# Yitran_IT900_Hutschiene_PIM7A_1_0.net
KiCad netlist of a schematic drawn in EAGLE
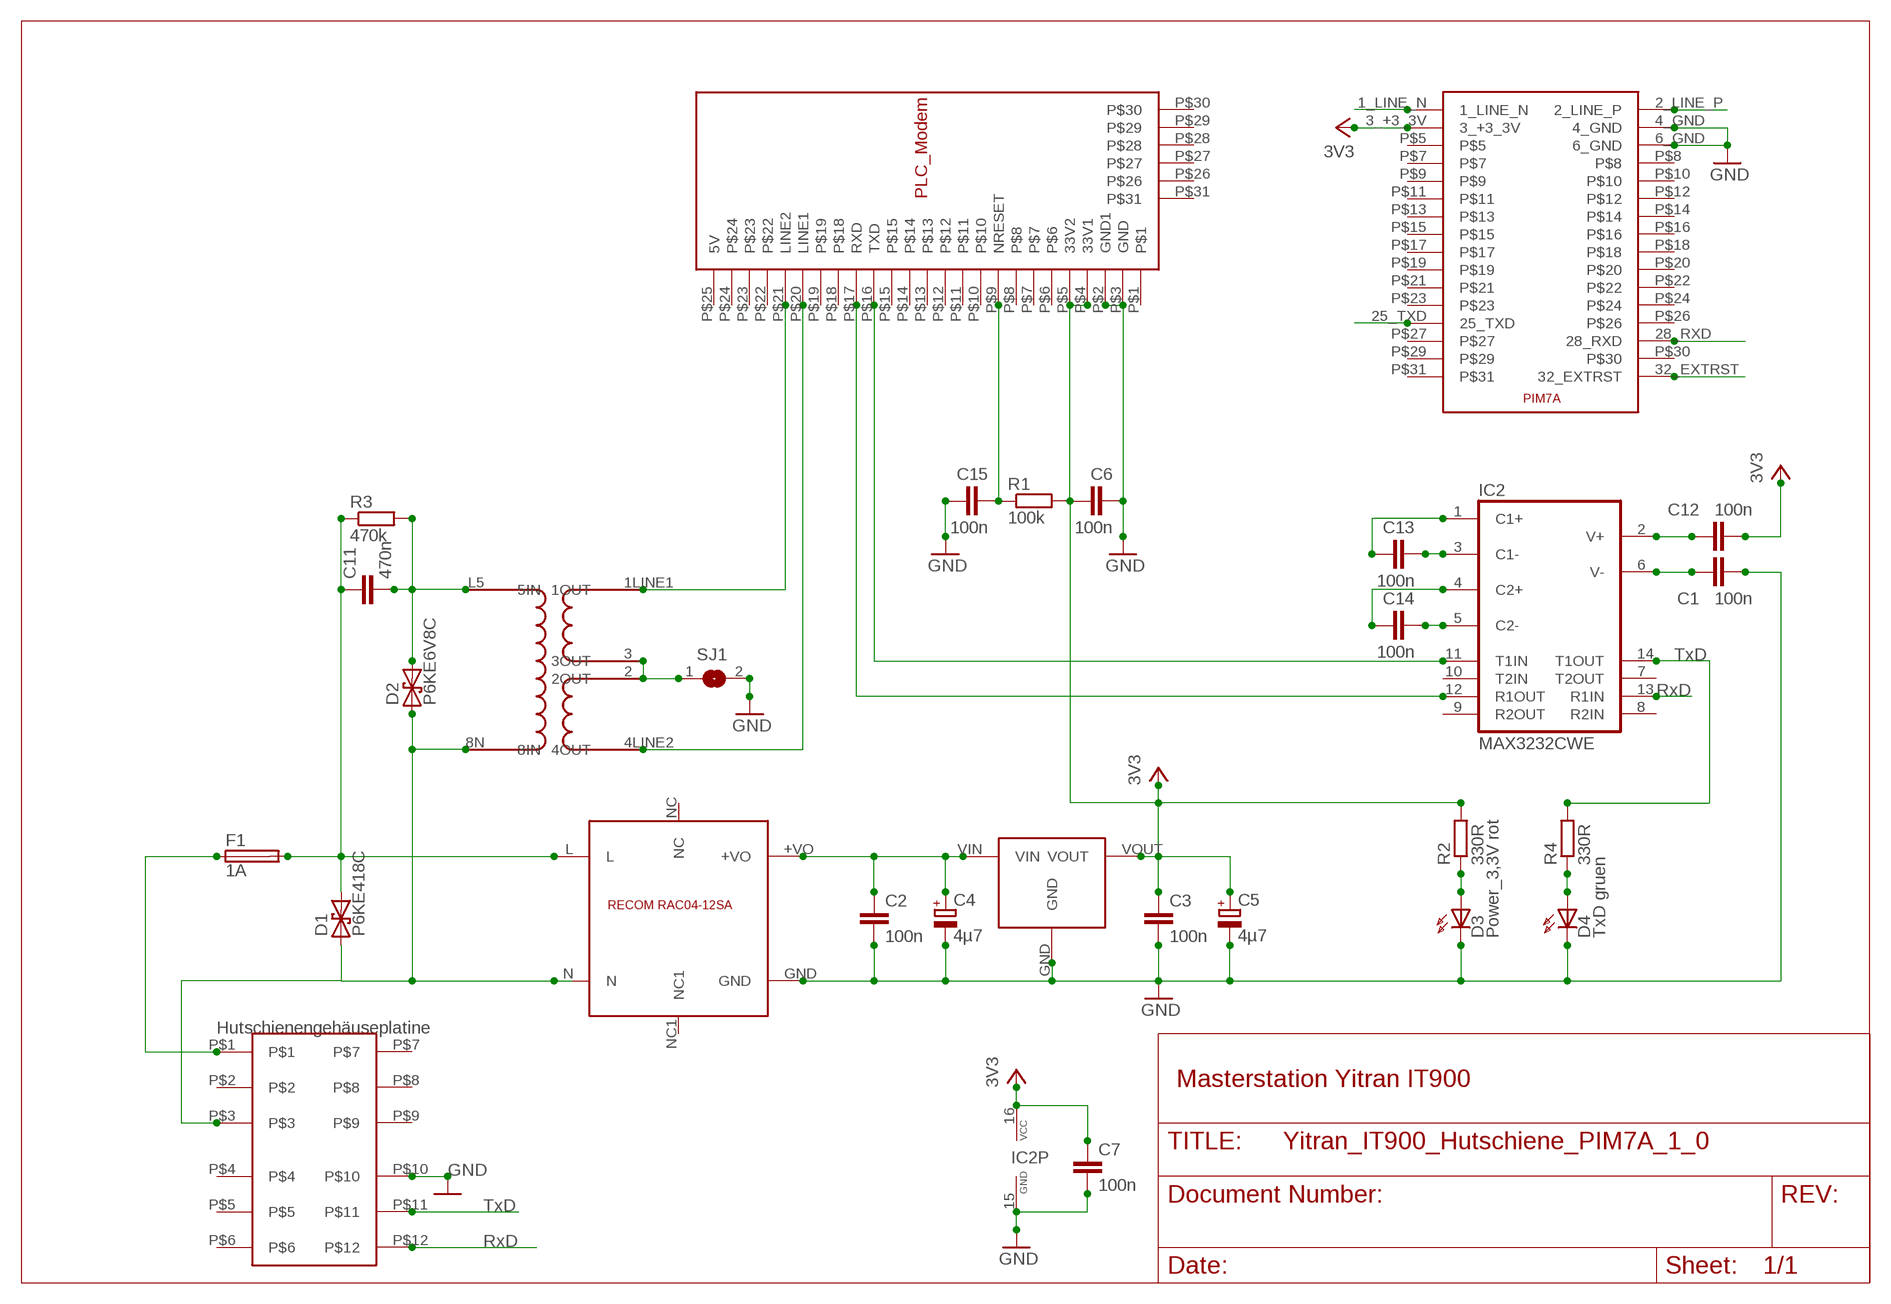
[diagram p0: schematic, sheet 1]

(export (version "E")
  (design (tool "Eeschema 10.0.6"))
  (components
    (comp (ref "C1")
      (value "100n")
      (footprint "eagle-import:C1206K")
      (libsource (lib "eagle-import") (part "C-EUC1206K"))
    )
    (comp (ref "C2")
      (value "100n")
      (footprint "eagle-import:C1206K")
      (libsource (lib "eagle-import") (part "C-EUC1206K"))
    )
    (comp (ref "C3")
      (value "100n")
      (footprint "eagle-import:C1206K")
      (libsource (lib "eagle-import") (part "C-EUC1206K"))
    )
    (comp (ref "C4")
      (value "4µ7")
      (footprint "eagle-import:E2,5-5")
      (libsource (lib "eagle-import") (part "CPOL-EUE2.5-5"))
    )
    (comp (ref "C5")
      (value "4µ7")
      (footprint "eagle-import:E2,5-5")
      (libsource (lib "eagle-import") (part "CPOL-EUE2.5-5"))
    )
    (comp (ref "C6")
      (value "100n")
      (footprint "eagle-import:C1206K")
      (libsource (lib "eagle-import") (part "C-EUC1206K"))
    )
    (comp (ref "C7")
      (value "100n")
      (footprint "eagle-import:C1206K")
      (libsource (lib "eagle-import") (part "C-EUC1206K"))
    )
    (comp (ref "C11")
      (value "470n")
      (footprint "eagle-import:C150-091X182")
      (libsource (lib "eagle-import") (part "C-EU150-091X182"))
    )
    (comp (ref "C12")
      (value "100n")
      (footprint "eagle-import:C1206K")
      (libsource (lib "eagle-import") (part "C-EUC1206K"))
    )
    (comp (ref "C13")
      (value "100n")
      (footprint "eagle-import:C1206K")
      (libsource (lib "eagle-import") (part "C-EUC1206K"))
    )
    (comp (ref "C14")
      (value "100n")
      (footprint "eagle-import:C1206K")
      (libsource (lib "eagle-import") (part "C-EUC1206K"))
    )
    (comp (ref "C15")
      (value "100n")
      (footprint "eagle-import:C1206K")
      (libsource (lib "eagle-import") (part "C-EUC1206K"))
    )
    (comp (ref "D1")
      (value "P6KE418C")
      (footprint "eagle-import:CB417-15")
      (libsource (lib "eagle-import") (part "P6KEXXC"))
    )
    (comp (ref "D2")
      (value "P6KE6V8C")
      (footprint "eagle-import:CB417-15")
      (libsource (lib "eagle-import") (part "P6KEXXC"))
    )
    (comp (ref "D3")
      (value "Power_3,3V rot")
      (footprint "eagle-import:HLMP6")
      (fields (field (name "MF") "AGILENT TECHNOLOGIES") (field (name "MPN") "HLMP-6500"))
      (libsource (lib "eagle-import") (part "HLMP6"))
    )
    (comp (ref "D4")
      (value "TxD gruen")
      (footprint "eagle-import:HLMP6")
      (fields (field (name "MF") "AGILENT TECHNOLOGIES") (field (name "MPN") "HLMP-6500"))
      (libsource (lib "eagle-import") (part "HLMP6"))
    )
    (comp (ref "F1")
      (value "1A")
      (footprint "eagle-import:TR5")
      (libsource (lib "eagle-import") (part "TR5"))
    )
    (comp (ref "IC2")
      (value "MAX3232CWE")
      (footprint "eagle-import:SO16L")
      (fields (field (name "MF") "MAXIM") (field (name "MPN") "MAX3232CWE+"))
      (libsource (lib "eagle-import") (part "MAX3232WEC"))
    )
    (comp (ref "R1")
      (value "100k")
      (footprint "eagle-import:M1406")
      (libsource (lib "eagle-import") (part "R-EU_M1406"))
    )
    (comp (ref "R2")
      (value "330R")
      (footprint "eagle-import:R1206")
      (libsource (lib "eagle-import") (part "R-EU_R1206"))
    )
    (comp (ref "R3")
      (value "470k")
      (footprint "eagle-import:0309_10")
      (libsource (lib "eagle-import") (part "R-EU_0309/10"))
    )
    (comp (ref "R4")
      (value "330R")
      (footprint "eagle-import:R1206")
      (libsource (lib "eagle-import") (part "R-EU_R1206"))
    )
    (comp (ref "SJ1")
      (value "SJW")
      (footprint "eagle-import:SJW")
      (libsource (lib "eagle-import") (part "SJW"))
    )
    (comp (ref "U$1")
      (value "RECOM_783_3")
      (footprint "eagle-import:RECOM785X")
      (libsource (lib "eagle-import") (part "RECOM_785_05"))
    )
    (comp (ref "U$2")
      (value "LDG-A-12")
      (footprint "eagle-import:LDG-A-12")
      (libsource (lib "eagle-import") (part "LDG-A-12"))
    )
    (comp (ref "U$3")
      (value "MODEMSTECKER")
      (footprint "eagle-import:MODEM_FUSS")
      (libsource (lib "eagle-import") (part "MODEMSTECKER"))
    )
    (comp (ref "U$4")
      (value "IT900PIM7A")
      (footprint "eagle-import:IT900PIM7A")
      (libsource (lib "eagle-import") (part "IT900PIM7A"))
    )
    (comp (ref "U$9")
      (value "RECOM_RAC04_12SA")
      (footprint "eagle-import:RAC04_12SA")
      (libsource (lib "eagle-import") (part "RECOM_RAC04_12SA"))
    )
    (comp (ref "U$10")
      (value "PLC_UEBERTRAGER_V2")
      (footprint "eagle-import:PLC-UEBERTRAGER_V2")
      (libsource (lib "eagle-import") (part "PLC_UEBERTRAGER_V2"))
    )
  )
  (nets
    (net (code "1") (name "/EXTRST") (class "Default")
      (node (ref "C15") (pin "2") (pinfunction "2_2") (pintype "passive"))
      (node (ref "R1") (pin "1") (pinfunction "1_1") (pintype "passive"))
      (node (ref "U$3") (pin "P$9") (pinfunction "NRESET_P$9") (pintype "bidirectional"))
      (node (ref "U$4") (pin "32_EXTRST") (pinfunction "32_EXTRST_32_EXTRST") (pintype "bidirectional"))
    )
    (net (code "2") (name "/LINE1") (class "Default")
      (node (ref "U$10") (pin "4LINE2") (pinfunction "4OUT_4LINE2") (pintype "output"))
      (node (ref "U$3") (pin "P$20") (pinfunction "LINE1_P$20") (pintype "bidirectional"))
      (node (ref "U$4") (pin "1_LINE_N") (pinfunction "1_LINE_N_1_LINE_N") (pintype "bidirectional"))
    )
    (net (code "3") (name "/LINE2") (class "Default")
      (node (ref "U$10") (pin "1LINE1") (pinfunction "1OUT_1LINE1") (pintype "output"))
      (node (ref "U$3") (pin "P$21") (pinfunction "LINE2_P$21") (pintype "bidirectional"))
      (node (ref "U$4") (pin "2_LINE_P") (pinfunction "2_LINE_P_2_LINE_P") (pintype "bidirectional"))
    )
    (net (code "4") (name "/RX") (class "Default")
      (node (ref "IC2") (pin "12") (pinfunction "R1OUT_12") (pintype "output"))
      (node (ref "U$3") (pin "P$17") (pinfunction "RXD_P$17") (pintype "bidirectional"))
      (node (ref "U$4") (pin "28_RXD") (pinfunction "28_RXD_28_RXD") (pintype "bidirectional"))
    )
    (net (code "5") (name "/RXD") (class "Default")
      (node (ref "IC2") (pin "13") (pinfunction "R1IN_13") (pintype "input"))
      (node (ref "U$2") (pin "P$12") (pinfunction "P$12_P$12") (pintype "bidirectional"))
    )
    (net (code "6") (name "/TX") (class "Default")
      (node (ref "IC2") (pin "11") (pinfunction "T1IN_11") (pintype "input"))
      (node (ref "U$3") (pin "P$16") (pinfunction "TXD_P$16") (pintype "bidirectional"))
      (node (ref "U$4") (pin "25_TXD") (pinfunction "25_TXD_25_TXD") (pintype "bidirectional"))
    )
    (net (code "7") (name "/TXD") (class "Default")
      (node (ref "IC2") (pin "14") (pinfunction "T1OUT_14") (pintype "output"))
      (node (ref "R4") (pin "2") (pinfunction "2_2") (pintype "passive"))
      (node (ref "U$2") (pin "P$11") (pinfunction "P$11_P$11") (pintype "bidirectional"))
    )
    (net (code "8") (name "3V3") (class "Default")
      (node (ref "C12") (pin "2") (pinfunction "2_2") (pintype "passive"))
      (node (ref "C3") (pin "1") (pinfunction "1_1") (pintype "passive"))
      (node (ref "C5") (pin "+") (pinfunction "+_+") (pintype "passive"))
      (node (ref "C6") (pin "1") (pinfunction "1_1") (pintype "passive"))
      (node (ref "C7") (pin "1") (pinfunction "1_1") (pintype "passive"))
      (node (ref "IC2") (pin "16") (pinfunction "VCC_16") (pintype "power_in"))
      (node (ref "R1") (pin "2") (pinfunction "2_2") (pintype "passive"))
      (node (ref "R2") (pin "2") (pinfunction "2_2") (pintype "passive"))
      (node (ref "U$1") (pin "VOUT") (pinfunction "VOUT_VOUT") (pintype "bidirectional"))
      (node (ref "U$3") (pin "P$4") (pinfunction "33V1_P$4") (pintype "bidirectional"))
      (node (ref "U$3") (pin "P$5") (pinfunction "33V2_P$5") (pintype "bidirectional"))
      (node (ref "U$4") (pin "3_+3_3V") (pinfunction "3_+3_3V_3_+3_3V") (pintype "bidirectional"))
    )
    (net (code "9") (name "GND") (class "Default")
      (node (ref "C1") (pin "2") (pinfunction "2_2") (pintype "passive"))
      (node (ref "C15") (pin "1") (pinfunction "1_1") (pintype "passive"))
      (node (ref "C2") (pin "2") (pinfunction "2_2") (pintype "passive"))
      (node (ref "C3") (pin "2") (pinfunction "2_2") (pintype "passive"))
      (node (ref "C4") (pin "-") (pinfunction "-_-") (pintype "passive"))
      (node (ref "C5") (pin "-") (pinfunction "-_-") (pintype "passive"))
      (node (ref "C6") (pin "2") (pinfunction "2_2") (pintype "passive"))
      (node (ref "C7") (pin "2") (pinfunction "2_2") (pintype "passive"))
      (node (ref "D3") (pin "K") (pinfunction "K_K") (pintype "passive"))
      (node (ref "D4") (pin "K") (pinfunction "K_K") (pintype "passive"))
      (node (ref "IC2") (pin "15") (pinfunction "GND_15") (pintype "power_in"))
      (node (ref "SJ1") (pin "2") (pinfunction "2_2") (pintype "passive"))
      (node (ref "U$1") (pin "GND") (pinfunction "GND_GND") (pintype "bidirectional"))
      (node (ref "U$2") (pin "P$10") (pinfunction "P$10_P$10") (pintype "bidirectional"))
      (node (ref "U$3") (pin "P$2") (pinfunction "GND1_P$2") (pintype "bidirectional"))
      (node (ref "U$3") (pin "P$3") (pinfunction "GND_P$3") (pintype "bidirectional"))
      (node (ref "U$4") (pin "4_GND") (pinfunction "4_GND_4_GND") (pintype "bidirectional"))
      (node (ref "U$4") (pin "6_GND") (pinfunction "6_GND_6_GND") (pintype "bidirectional"))
      (node (ref "U$9") (pin "GND") (pinfunction "GND_GND") (pintype "bidirectional"))
    )
    (net (code "10") (name "Net-(C2-Pad1)") (class "Default")
      (node (ref "C2") (pin "1") (pinfunction "1_1") (pintype "passive"))
      (node (ref "C4") (pin "+") (pinfunction "+_+") (pintype "passive"))
      (node (ref "U$1") (pin "VIN") (pinfunction "VIN_VIN") (pintype "bidirectional"))
      (node (ref "U$9") (pin "+VO") (pinfunction "+VO_+VO") (pintype "bidirectional"))
    )
    (net (code "11") (name "Net-(D1-1)") (class "Default")
      (node (ref "D1") (pin "A") (pinfunction "1_A") (pintype "passive"))
      (node (ref "D2") (pin "A") (pinfunction "1_A") (pintype "passive"))
      (node (ref "U$10") (pin "8N") (pinfunction "8IN_8N") (pintype "input"))
      (node (ref "U$2") (pin "P$3") (pinfunction "P$3_P$3") (pintype "bidirectional"))
      (node (ref "U$9") (pin "N") (pinfunction "N_N") (pintype "bidirectional"))
    )
    (net (code "12") (name "Net-(D1-2)") (class "Default")
      (node (ref "C11") (pin "1") (pinfunction "1_1") (pintype "passive"))
      (node (ref "D1") (pin "C") (pinfunction "2_C") (pintype "passive"))
      (node (ref "F1") (pin "2") (pinfunction "2_2") (pintype "passive"))
      (node (ref "R3") (pin "1") (pinfunction "1_1") (pintype "passive"))
      (node (ref "U$9") (pin "L") (pinfunction "L_L") (pintype "bidirectional"))
    )
    (net (code "13") (name "Net-(D2-2)") (class "Default")
      (node (ref "C11") (pin "2") (pinfunction "2_2") (pintype "passive"))
      (node (ref "D2") (pin "C") (pinfunction "2_C") (pintype "passive"))
      (node (ref "R3") (pin "2") (pinfunction "2_2") (pintype "passive"))
      (node (ref "U$10") (pin "L5") (pinfunction "5IN_L5") (pintype "input"))
    )
    (net (code "14") (name "Net-(D3-PadA)") (class "Default")
      (node (ref "D3") (pin "A") (pinfunction "A_A") (pintype "passive"))
      (node (ref "R2") (pin "1") (pinfunction "1_1") (pintype "passive"))
    )
    (net (code "15") (name "Net-(D4-PadA)") (class "Default")
      (node (ref "D4") (pin "A") (pinfunction "A_A") (pintype "passive"))
      (node (ref "R4") (pin "1") (pinfunction "1_1") (pintype "passive"))
    )
    (net (code "16") (name "Net-(F1-Pad1)") (class "Default")
      (node (ref "F1") (pin "1") (pinfunction "1_1") (pintype "passive"))
      (node (ref "U$2") (pin "P$1") (pinfunction "P$1_P$1") (pintype "bidirectional"))
    )
    (net (code "17") (name "Net-(IC2A-C1+)") (class "Default")
      (node (ref "C13") (pin "1") (pinfunction "1_1") (pintype "passive"))
      (node (ref "IC2") (pin "1") (pinfunction "C1+_1") (pintype "bidirectional"))
    )
    (net (code "18") (name "Net-(IC2A-C1-)") (class "Default")
      (node (ref "C13") (pin "2") (pinfunction "2_2") (pintype "passive"))
      (node (ref "IC2") (pin "3") (pinfunction "C1-_3") (pintype "bidirectional"))
    )
    (net (code "19") (name "Net-(IC2A-C2+)") (class "Default")
      (node (ref "C14") (pin "1") (pinfunction "1_1") (pintype "passive"))
      (node (ref "IC2") (pin "4") (pinfunction "C2+_4") (pintype "bidirectional"))
    )
    (net (code "20") (name "Net-(IC2A-C2-)") (class "Default")
      (node (ref "C14") (pin "2") (pinfunction "2_2") (pintype "passive"))
      (node (ref "IC2") (pin "5") (pinfunction "C2-_5") (pintype "bidirectional"))
    )
    (net (code "21") (name "Net-(IC2A-V+)") (class "Default")
      (node (ref "C12") (pin "1") (pinfunction "1_1") (pintype "passive"))
      (node (ref "IC2") (pin "2") (pinfunction "V+_2") (pintype "bidirectional"))
    )
    (net (code "22") (name "Net-(IC2A-V-)") (class "Default")
      (node (ref "C1") (pin "1") (pinfunction "1_1") (pintype "passive"))
      (node (ref "IC2") (pin "6") (pinfunction "V-_6") (pintype "bidirectional"))
    )
    (net (code "23") (name "Net-(U$10-2OUT)") (class "Default")
      (node (ref "SJ1") (pin "1") (pinfunction "1_1") (pintype "passive"))
      (node (ref "U$10") (pin "2") (pinfunction "2OUT_2") (pintype "output"))
      (node (ref "U$10") (pin "3") (pinfunction "3OUT_3") (pintype "output"))
    )
    (net (code "24") (name "unconnected-(IC2A-R2IN-Pad8)") (class "Default")
      (node (ref "IC2") (pin "8") (pinfunction "R2IN_8") (pintype "input"))
    )
    (net (code "25") (name "unconnected-(IC2A-R2OUT-Pad9)") (class "Default")
      (node (ref "IC2") (pin "9") (pinfunction "R2OUT_9") (pintype "output"))
    )
    (net (code "26") (name "unconnected-(IC2A-T2IN-Pad10)") (class "Default")
      (node (ref "IC2") (pin "10") (pinfunction "T2IN_10") (pintype "input"))
    )
    (net (code "27") (name "unconnected-(IC2A-T2OUT-Pad7)") (class "Default")
      (node (ref "IC2") (pin "7") (pinfunction "T2OUT_7") (pintype "output"))
    )
    (net (code "28") (name "unconnected-(U$2-PadP$2)") (class "Default")
      (node (ref "U$2") (pin "P$2") (pinfunction "P$2_P$2") (pintype "bidirectional"))
    )
    (net (code "29") (name "unconnected-(U$2-PadP$4)") (class "Default")
      (node (ref "U$2") (pin "P$4") (pinfunction "P$4_P$4") (pintype "bidirectional"))
    )
    (net (code "30") (name "unconnected-(U$2-PadP$5)") (class "Default")
      (node (ref "U$2") (pin "P$5") (pinfunction "P$5_P$5") (pintype "bidirectional"))
    )
    (net (code "31") (name "unconnected-(U$2-PadP$6)") (class "Default")
      (node (ref "U$2") (pin "P$6") (pinfunction "P$6_P$6") (pintype "bidirectional"))
    )
    (net (code "32") (name "unconnected-(U$2-PadP$7)") (class "Default")
      (node (ref "U$2") (pin "P$7") (pinfunction "P$7_P$7") (pintype "bidirectional"))
    )
    (net (code "33") (name "unconnected-(U$2-PadP$8)") (class "Default")
      (node (ref "U$2") (pin "P$8") (pinfunction "P$8_P$8") (pintype "bidirectional"))
    )
    (net (code "34") (name "unconnected-(U$2-PadP$9)") (class "Default")
      (node (ref "U$2") (pin "P$9") (pinfunction "P$9_P$9") (pintype "bidirectional"))
    )
    (net (code "35") (name "unconnected-(U$3-5V-PadP$25)") (class "Default")
      (node (ref "U$3") (pin "P$25") (pinfunction "5V_P$25") (pintype "bidirectional"))
    )
    (net (code "36") (name "unconnected-(U$3-PadP$1)") (class "Default")
      (node (ref "U$3") (pin "P$1") (pinfunction "P$1_P$1") (pintype "bidirectional"))
    )
    (net (code "37") (name "unconnected-(U$3-PadP$6)") (class "Default")
      (node (ref "U$3") (pin "P$6") (pinfunction "P$6_P$6") (pintype "bidirectional"))
    )
    (net (code "38") (name "unconnected-(U$3-PadP$7)") (class "Default")
      (node (ref "U$3") (pin "P$7") (pinfunction "P$7_P$7") (pintype "bidirectional"))
    )
    (net (code "39") (name "unconnected-(U$3-PadP$8)") (class "Default")
      (node (ref "U$3") (pin "P$8") (pinfunction "P$8_P$8") (pintype "bidirectional"))
    )
    (net (code "40") (name "unconnected-(U$3-PadP$10)") (class "Default")
      (node (ref "U$3") (pin "P$10") (pinfunction "P$10_P$10") (pintype "bidirectional"))
    )
    (net (code "41") (name "unconnected-(U$3-PadP$11)") (class "Default")
      (node (ref "U$3") (pin "P$11") (pinfunction "P$11_P$11") (pintype "bidirectional"))
    )
    (net (code "42") (name "unconnected-(U$3-PadP$12)") (class "Default")
      (node (ref "U$3") (pin "P$12") (pinfunction "P$12_P$12") (pintype "bidirectional"))
    )
    (net (code "43") (name "unconnected-(U$3-PadP$13)") (class "Default")
      (node (ref "U$3") (pin "P$13") (pinfunction "P$13_P$13") (pintype "bidirectional"))
    )
    (net (code "44") (name "unconnected-(U$3-PadP$14)") (class "Default")
      (node (ref "U$3") (pin "P$14") (pinfunction "P$14_P$14") (pintype "bidirectional"))
    )
    (net (code "45") (name "unconnected-(U$3-PadP$15)") (class "Default")
      (node (ref "U$3") (pin "P$15") (pinfunction "P$15_P$15") (pintype "bidirectional"))
    )
    (net (code "46") (name "unconnected-(U$3-PadP$18)") (class "Default")
      (node (ref "U$3") (pin "P$18") (pinfunction "P$18_P$18") (pintype "bidirectional"))
    )
    (net (code "47") (name "unconnected-(U$3-PadP$19)") (class "Default")
      (node (ref "U$3") (pin "P$19") (pinfunction "P$19_P$19") (pintype "bidirectional"))
    )
    (net (code "48") (name "unconnected-(U$3-PadP$22)") (class "Default")
      (node (ref "U$3") (pin "P$22") (pinfunction "P$22_P$22") (pintype "bidirectional"))
    )
    (net (code "49") (name "unconnected-(U$3-PadP$23)") (class "Default")
      (node (ref "U$3") (pin "P$23") (pinfunction "P$23_P$23") (pintype "bidirectional"))
    )
    (net (code "50") (name "unconnected-(U$3-PadP$24)") (class "Default")
      (node (ref "U$3") (pin "P$24") (pinfunction "P$24_P$24") (pintype "bidirectional"))
    )
    (net (code "51") (name "unconnected-(U$3-PadP$26)") (class "Default")
      (node (ref "U$3") (pin "P$26") (pinfunction "P$26_P$26") (pintype "bidirectional"))
    )
    (net (code "52") (name "unconnected-(U$3-PadP$27)") (class "Default")
      (node (ref "U$3") (pin "P$27") (pinfunction "P$27_P$27") (pintype "bidirectional"))
    )
    (net (code "53") (name "unconnected-(U$3-PadP$28)") (class "Default")
      (node (ref "U$3") (pin "P$28") (pinfunction "P$28_P$28") (pintype "bidirectional"))
    )
    (net (code "54") (name "unconnected-(U$3-PadP$29)") (class "Default")
      (node (ref "U$3") (pin "P$29") (pinfunction "P$29_P$29") (pintype "bidirectional"))
    )
    (net (code "55") (name "unconnected-(U$3-PadP$30)") (class "Default")
      (node (ref "U$3") (pin "P$30") (pinfunction "P$30_P$30") (pintype "bidirectional"))
    )
    (net (code "56") (name "unconnected-(U$3-PadP$31)") (class "Default")
      (node (ref "U$3") (pin "P$31") (pinfunction "P$31_P$31") (pintype "bidirectional"))
    )
    (net (code "57") (name "unconnected-(U$4-PadP$5)") (class "Default")
      (node (ref "U$4") (pin "P$5") (pinfunction "P$5_P$5") (pintype "bidirectional"))
    )
    (net (code "58") (name "unconnected-(U$4-PadP$7)") (class "Default")
      (node (ref "U$4") (pin "P$7") (pinfunction "P$7_P$7") (pintype "bidirectional"))
    )
    (net (code "59") (name "unconnected-(U$4-PadP$8)") (class "Default")
      (node (ref "U$4") (pin "P$8") (pinfunction "P$8_P$8") (pintype "bidirectional"))
    )
    (net (code "60") (name "unconnected-(U$4-PadP$9)") (class "Default")
      (node (ref "U$4") (pin "P$9") (pinfunction "P$9_P$9") (pintype "bidirectional"))
    )
    (net (code "61") (name "unconnected-(U$4-PadP$10)") (class "Default")
      (node (ref "U$4") (pin "P$10") (pinfunction "P$10_P$10") (pintype "bidirectional"))
    )
    (net (code "62") (name "unconnected-(U$4-PadP$11)") (class "Default")
      (node (ref "U$4") (pin "P$11") (pinfunction "P$11_P$11") (pintype "bidirectional"))
    )
    (net (code "63") (name "unconnected-(U$4-PadP$12)") (class "Default")
      (node (ref "U$4") (pin "P$12") (pinfunction "P$12_P$12") (pintype "bidirectional"))
    )
    (net (code "64") (name "unconnected-(U$4-PadP$13)") (class "Default")
      (node (ref "U$4") (pin "P$13") (pinfunction "P$13_P$13") (pintype "bidirectional"))
    )
    (net (code "65") (name "unconnected-(U$4-PadP$14)") (class "Default")
      (node (ref "U$4") (pin "P$14") (pinfunction "P$14_P$14") (pintype "bidirectional"))
    )
    (net (code "66") (name "unconnected-(U$4-PadP$15)") (class "Default")
      (node (ref "U$4") (pin "P$15") (pinfunction "P$15_P$15") (pintype "bidirectional"))
    )
    (net (code "67") (name "unconnected-(U$4-PadP$16)") (class "Default")
      (node (ref "U$4") (pin "P$16") (pinfunction "P$16_P$16") (pintype "bidirectional"))
    )
    (net (code "68") (name "unconnected-(U$4-PadP$17)") (class "Default")
      (node (ref "U$4") (pin "P$17") (pinfunction "P$17_P$17") (pintype "bidirectional"))
    )
    (net (code "69") (name "unconnected-(U$4-PadP$18)") (class "Default")
      (node (ref "U$4") (pin "P$18") (pinfunction "P$18_P$18") (pintype "bidirectional"))
    )
    (net (code "70") (name "unconnected-(U$4-PadP$19)") (class "Default")
      (node (ref "U$4") (pin "P$19") (pinfunction "P$19_P$19") (pintype "bidirectional"))
    )
    (net (code "71") (name "unconnected-(U$4-PadP$20)") (class "Default")
      (node (ref "U$4") (pin "P$20") (pinfunction "P$20_P$20") (pintype "bidirectional"))
    )
    (net (code "72") (name "unconnected-(U$4-PadP$21)") (class "Default")
      (node (ref "U$4") (pin "P$21") (pinfunction "P$21_P$21") (pintype "bidirectional"))
    )
    (net (code "73") (name "unconnected-(U$4-PadP$22)") (class "Default")
      (node (ref "U$4") (pin "P$22") (pinfunction "P$22_P$22") (pintype "bidirectional"))
    )
    (net (code "74") (name "unconnected-(U$4-PadP$23)") (class "Default")
      (node (ref "U$4") (pin "P$23") (pinfunction "P$23_P$23") (pintype "bidirectional"))
    )
    (net (code "75") (name "unconnected-(U$4-PadP$24)") (class "Default")
      (node (ref "U$4") (pin "P$24") (pinfunction "P$24_P$24") (pintype "bidirectional"))
    )
    (net (code "76") (name "unconnected-(U$4-PadP$26)") (class "Default")
      (node (ref "U$4") (pin "P$26") (pinfunction "P$26_P$26") (pintype "bidirectional"))
    )
    (net (code "77") (name "unconnected-(U$4-PadP$27)") (class "Default")
      (node (ref "U$4") (pin "P$27") (pinfunction "P$27_P$27") (pintype "bidirectional"))
    )
    (net (code "78") (name "unconnected-(U$4-PadP$29)") (class "Default")
      (node (ref "U$4") (pin "P$29") (pinfunction "P$29_P$29") (pintype "bidirectional"))
    )
    (net (code "79") (name "unconnected-(U$4-PadP$30)") (class "Default")
      (node (ref "U$4") (pin "P$30") (pinfunction "P$30_P$30") (pintype "bidirectional"))
    )
    (net (code "80") (name "unconnected-(U$4-PadP$31)") (class "Default")
      (node (ref "U$4") (pin "P$31") (pinfunction "P$31_P$31") (pintype "bidirectional"))
    )
    (net (code "81") (name "unconnected-(U$9-PadNC)") (class "Default")
      (node (ref "U$9") (pin "NC") (pinfunction "NC_NC") (pintype "bidirectional"))
    )
    (net (code "82") (name "unconnected-(U$9-PadNC1)") (class "Default")
      (node (ref "U$9") (pin "NC1") (pinfunction "NC1_NC1") (pintype "bidirectional"))
    )
  )
)
